# v1_3.net
KiCad netlist of a schematic drawn in EAGLE
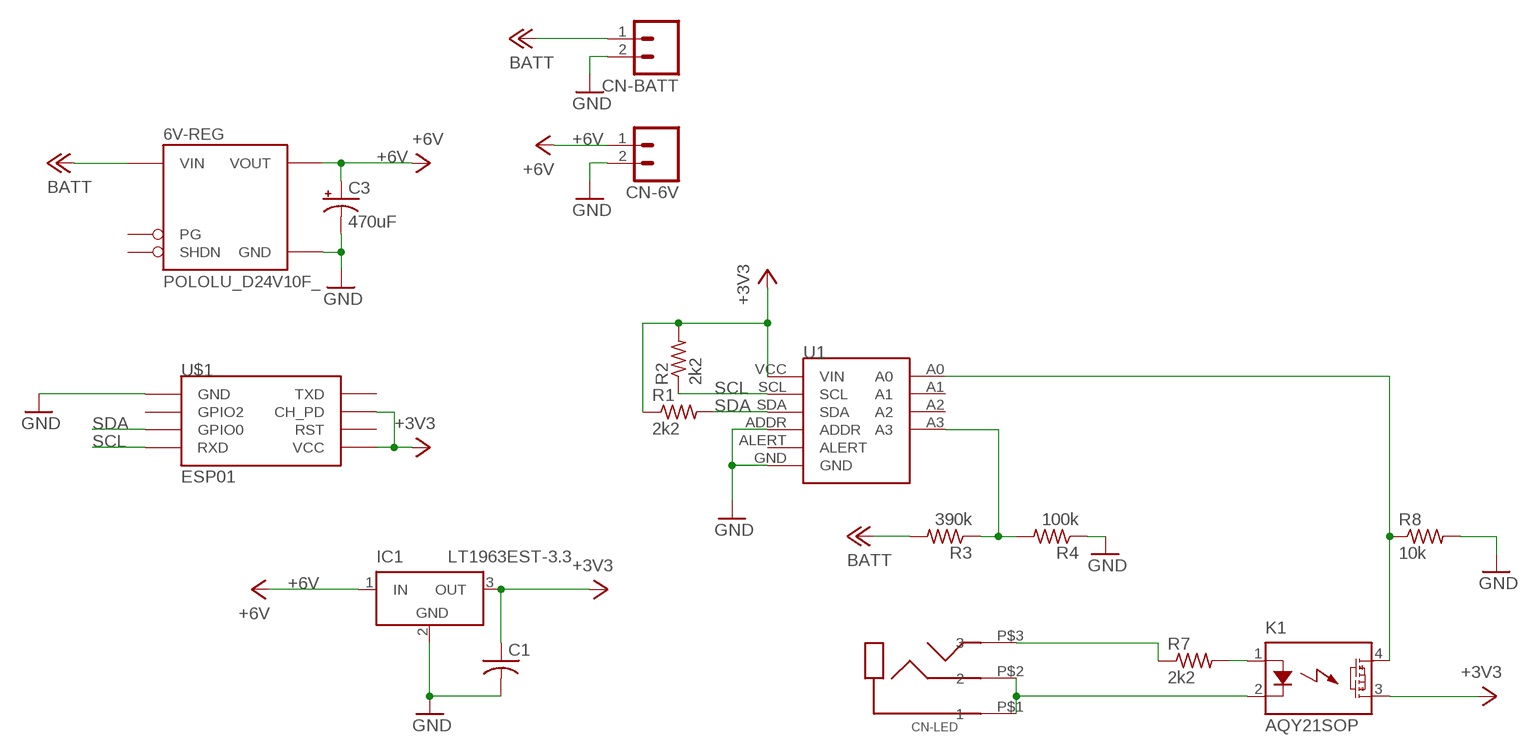
[diagram p0: schematic, sheet 1]

(export (version "E")
  (design (tool "Eeschema 10.0.6"))
  (components
    (comp (ref "6V-REG")
      (value "POLOLU_D24V10F_")
      (footprint "eagle-import:POLOLU_D24V10")
      (libsource (lib "eagle-import") (part "POLOLU_D24V10F_"))
    )
    (comp (ref "C1")
      (value "C-USC1210")
      (footprint "eagle-import:C1210")
      (libsource (lib "eagle-import") (part "C-USC1210"))
    )
    (comp (ref "C3")
      (value "470uF")
      (footprint "eagle-import:CPOL-RADIAL-2.5MM-6.5MM")
      (libsource (lib "eagle-import") (part "100UF-POLAR-RADIAL-2.5MM-25V-20%"))
    )
    (comp (ref "CN-6V")
      (value "M02")
      (footprint "eagle-import:02P")
      (libsource (lib "eagle-import") (part "M02"))
    )
    (comp (ref "CN-BATT")
      (value "M02")
      (footprint "eagle-import:02P")
      (libsource (lib "eagle-import") (part "M02"))
    )
    (comp (ref "CN-LED")
      (value "PJ-320B")
      (footprint "eagle-import:PJ-320B")
      (libsource (lib "eagle-import") (part "PJ-320B"))
    )
    (comp (ref "IC1")
      (value "LT1963EST-3.3")
      (footprint "eagle-import:SOT223")
      (libsource (lib "eagle-import") (part "LT1963EST-3.3"))
    )
    (comp (ref "K1")
      (value "AQY21SOP")
      (footprint "eagle-import:SOP04")
      (libsource (lib "eagle-import") (part "AQYSOP21"))
    )
    (comp (ref "R1")
      (value "2k2")
      (footprint "eagle-import:R0603")
      (libsource (lib "eagle-import") (part "R-US_R0603"))
    )
    (comp (ref "R2")
      (value "2k2")
      (footprint "eagle-import:R0603")
      (libsource (lib "eagle-import") (part "R-US_R0603"))
    )
    (comp (ref "R3")
      (value "390k")
      (footprint "eagle-import:R0603")
      (libsource (lib "eagle-import") (part "R-US_R0603"))
    )
    (comp (ref "R4")
      (value "100k")
      (footprint "eagle-import:R0603")
      (libsource (lib "eagle-import") (part "R-US_R0603"))
    )
    (comp (ref "R7")
      (value "2k2")
      (footprint "eagle-import:R0603")
      (libsource (lib "eagle-import") (part "R-US_R0603"))
    )
    (comp (ref "R8")
      (value "10k")
      (footprint "eagle-import:R0603")
      (libsource (lib "eagle-import") (part "R-US_R0603"))
    )
    (comp (ref "U$1")
      (value "ESP01")
      (footprint "eagle-import:ESP01")
      (libsource (lib "eagle-import") (part "ESP01"))
    )
    (comp (ref "U1")
      (value "GY-ADS1115THM")
      (footprint "eagle-import:GY-ADS1115-THM")
      (libsource (lib "eagle-import") (part "GY-ADS1115THM"))
    )
  )
  (nets
    (net (code "1") (name "+3V3") (class "Default")
      (node (ref "C1") (pin "1") (pinfunction "1_1") (pintype "passive"))
      (node (ref "IC1") (pin "3") (pinfunction "OUT_3") (pintype "output"))
      (node (ref "K1") (pin "3") (pinfunction "DS2_3") (pintype "passive"))
      (node (ref "R1") (pin "1") (pinfunction "1_1") (pintype "passive"))
      (node (ref "R2") (pin "2") (pinfunction "2_2") (pintype "passive"))
      (node (ref "U$1") (pin "CH_PD") (pinfunction "CH_PD_CH_PD") (pintype "bidirectional"))
      (node (ref "U$1") (pin "VCC") (pinfunction "VCC_VCC") (pintype "bidirectional"))
      (node (ref "U1") (pin "VCC") (pinfunction "VIN_VCC") (pintype "bidirectional"))
    )
    (net (code "2") (name "+6V") (class "Default")
      (node (ref "6V-REG") (pin "VOUT") (pinfunction "VOUT_VOUT") (pintype "output"))
      (node (ref "C3") (pin "1") (pinfunction "+_1") (pintype "passive"))
      (node (ref "CN-6V") (pin "1") (pinfunction "1_1") (pintype "passive"))
      (node (ref "IC1") (pin "1") (pinfunction "IN_1") (pintype "input"))
    )
    (net (code "3") (name "/SCL") (class "Default")
      (node (ref "R2") (pin "1") (pinfunction "1_1") (pintype "passive"))
      (node (ref "U$1") (pin "RX") (pinfunction "RXD_RX") (pintype "bidirectional"))
      (node (ref "U1") (pin "SCL") (pinfunction "SCL_SCL") (pintype "bidirectional"))
    )
    (net (code "4") (name "/SDA") (class "Default")
      (node (ref "R1") (pin "2") (pinfunction "2_2") (pintype "passive"))
      (node (ref "U$1") (pin "GPIO0") (pinfunction "GPIO0_GPIO0") (pintype "bidirectional"))
      (node (ref "U1") (pin "SDA") (pinfunction "SDA_SDA") (pintype "bidirectional"))
    )
    (net (code "5") (name "BATT") (class "Default")
      (node (ref "6V-REG") (pin "VIN") (pinfunction "VIN_VIN") (pintype "power_in"))
      (node (ref "CN-BATT") (pin "1") (pinfunction "1_1") (pintype "passive"))
      (node (ref "R3") (pin "2") (pinfunction "2_2") (pintype "passive"))
    )
    (net (code "6") (name "GND") (class "Default")
      (node (ref "6V-REG") (pin "GND") (pinfunction "GND_GND") (pintype "power_in"))
      (node (ref "C1") (pin "2") (pinfunction "2_2") (pintype "passive"))
      (node (ref "C3") (pin "2") (pinfunction "-_2") (pintype "passive"))
      (node (ref "CN-6V") (pin "2") (pinfunction "2_2") (pintype "passive"))
      (node (ref "CN-BATT") (pin "2") (pinfunction "2_2") (pintype "passive"))
      (node (ref "IC1") (pin "2") (pinfunction "GND_2") (pintype "power_in"))
      (node (ref "R4") (pin "1") (pinfunction "1_1") (pintype "passive"))
      (node (ref "R8") (pin "2") (pinfunction "2_2") (pintype "passive"))
      (node (ref "U$1") (pin "GND") (pinfunction "GND_GND") (pintype "bidirectional"))
      (node (ref "U1") (pin "ADDR") (pinfunction "ADDR_ADDR") (pintype "bidirectional"))
      (node (ref "U1") (pin "GND") (pinfunction "GND_GND") (pintype "bidirectional"))
    )
    (net (code "7") (name "Net-(CN-LED-1)") (class "Default")
      (node (ref "CN-LED") (pin "P$1") (pinfunction "1_P$1") (pintype "bidirectional"))
      (node (ref "CN-LED") (pin "P$2") (pinfunction "2_P$2") (pintype "bidirectional"))
      (node (ref "K1") (pin "2") (pinfunction "K_2") (pintype "passive"))
    )
    (net (code "8") (name "Net-(CN-LED-3)") (class "Default")
      (node (ref "CN-LED") (pin "P$3") (pinfunction "3_P$3") (pintype "bidirectional"))
      (node (ref "R7") (pin "1") (pinfunction "1_1") (pintype "passive"))
    )
    (net (code "9") (name "Net-(K1-A)") (class "Default")
      (node (ref "K1") (pin "1") (pinfunction "A_1") (pintype "passive"))
      (node (ref "R7") (pin "2") (pinfunction "2_2") (pintype "passive"))
    )
    (net (code "10") (name "Net-(K1-DS1)") (class "Default")
      (node (ref "K1") (pin "4") (pinfunction "DS1_4") (pintype "passive"))
      (node (ref "R8") (pin "1") (pinfunction "1_1") (pintype "passive"))
      (node (ref "U1") (pin "A0") (pinfunction "A0_A0") (pintype "bidirectional"))
    )
    (net (code "11") (name "Net-(R3-Pad1)") (class "Default")
      (node (ref "R3") (pin "1") (pinfunction "1_1") (pintype "passive"))
      (node (ref "R4") (pin "2") (pinfunction "2_2") (pintype "passive"))
      (node (ref "U1") (pin "A3") (pinfunction "A3_A3") (pintype "bidirectional"))
    )
    (net (code "12") (name "unconnected-(6V-REG-PadPG)") (class "Default")
      (node (ref "6V-REG") (pin "PG") (pinfunction "PG_PG") (pintype "output"))
    )
    (net (code "13") (name "unconnected-(6V-REG-PadSHDN)") (class "Default")
      (node (ref "6V-REG") (pin "SHDN") (pinfunction "SHDN_SHDN") (pintype "input"))
    )
    (net (code "14") (name "unconnected-(U$1-PadGPIO2)") (class "Default")
      (node (ref "U$1") (pin "GPIO2") (pinfunction "GPIO2_GPIO2") (pintype "bidirectional"))
    )
    (net (code "15") (name "unconnected-(U$1-PadRST)") (class "Default")
      (node (ref "U$1") (pin "RST") (pinfunction "RST_RST") (pintype "bidirectional"))
    )
    (net (code "16") (name "unconnected-(U$1-TXD-PadTX)") (class "Default")
      (node (ref "U$1") (pin "TX") (pinfunction "TXD_TX") (pintype "bidirectional"))
    )
    (net (code "17") (name "unconnected-(U1-PadA1)") (class "Default")
      (node (ref "U1") (pin "A1") (pinfunction "A1_A1") (pintype "bidirectional"))
    )
    (net (code "18") (name "unconnected-(U1-PadA2)") (class "Default")
      (node (ref "U1") (pin "A2") (pinfunction "A2_A2") (pintype "bidirectional"))
    )
    (net (code "19") (name "unconnected-(U1-PadALERT)") (class "Default")
      (node (ref "U1") (pin "ALERT") (pinfunction "ALERT_ALERT") (pintype "bidirectional"))
    )
  )
)
